# Microcontroller_board_Photodiode_plate.net
KiCad netlist of a schematic drawn in EasyEDA
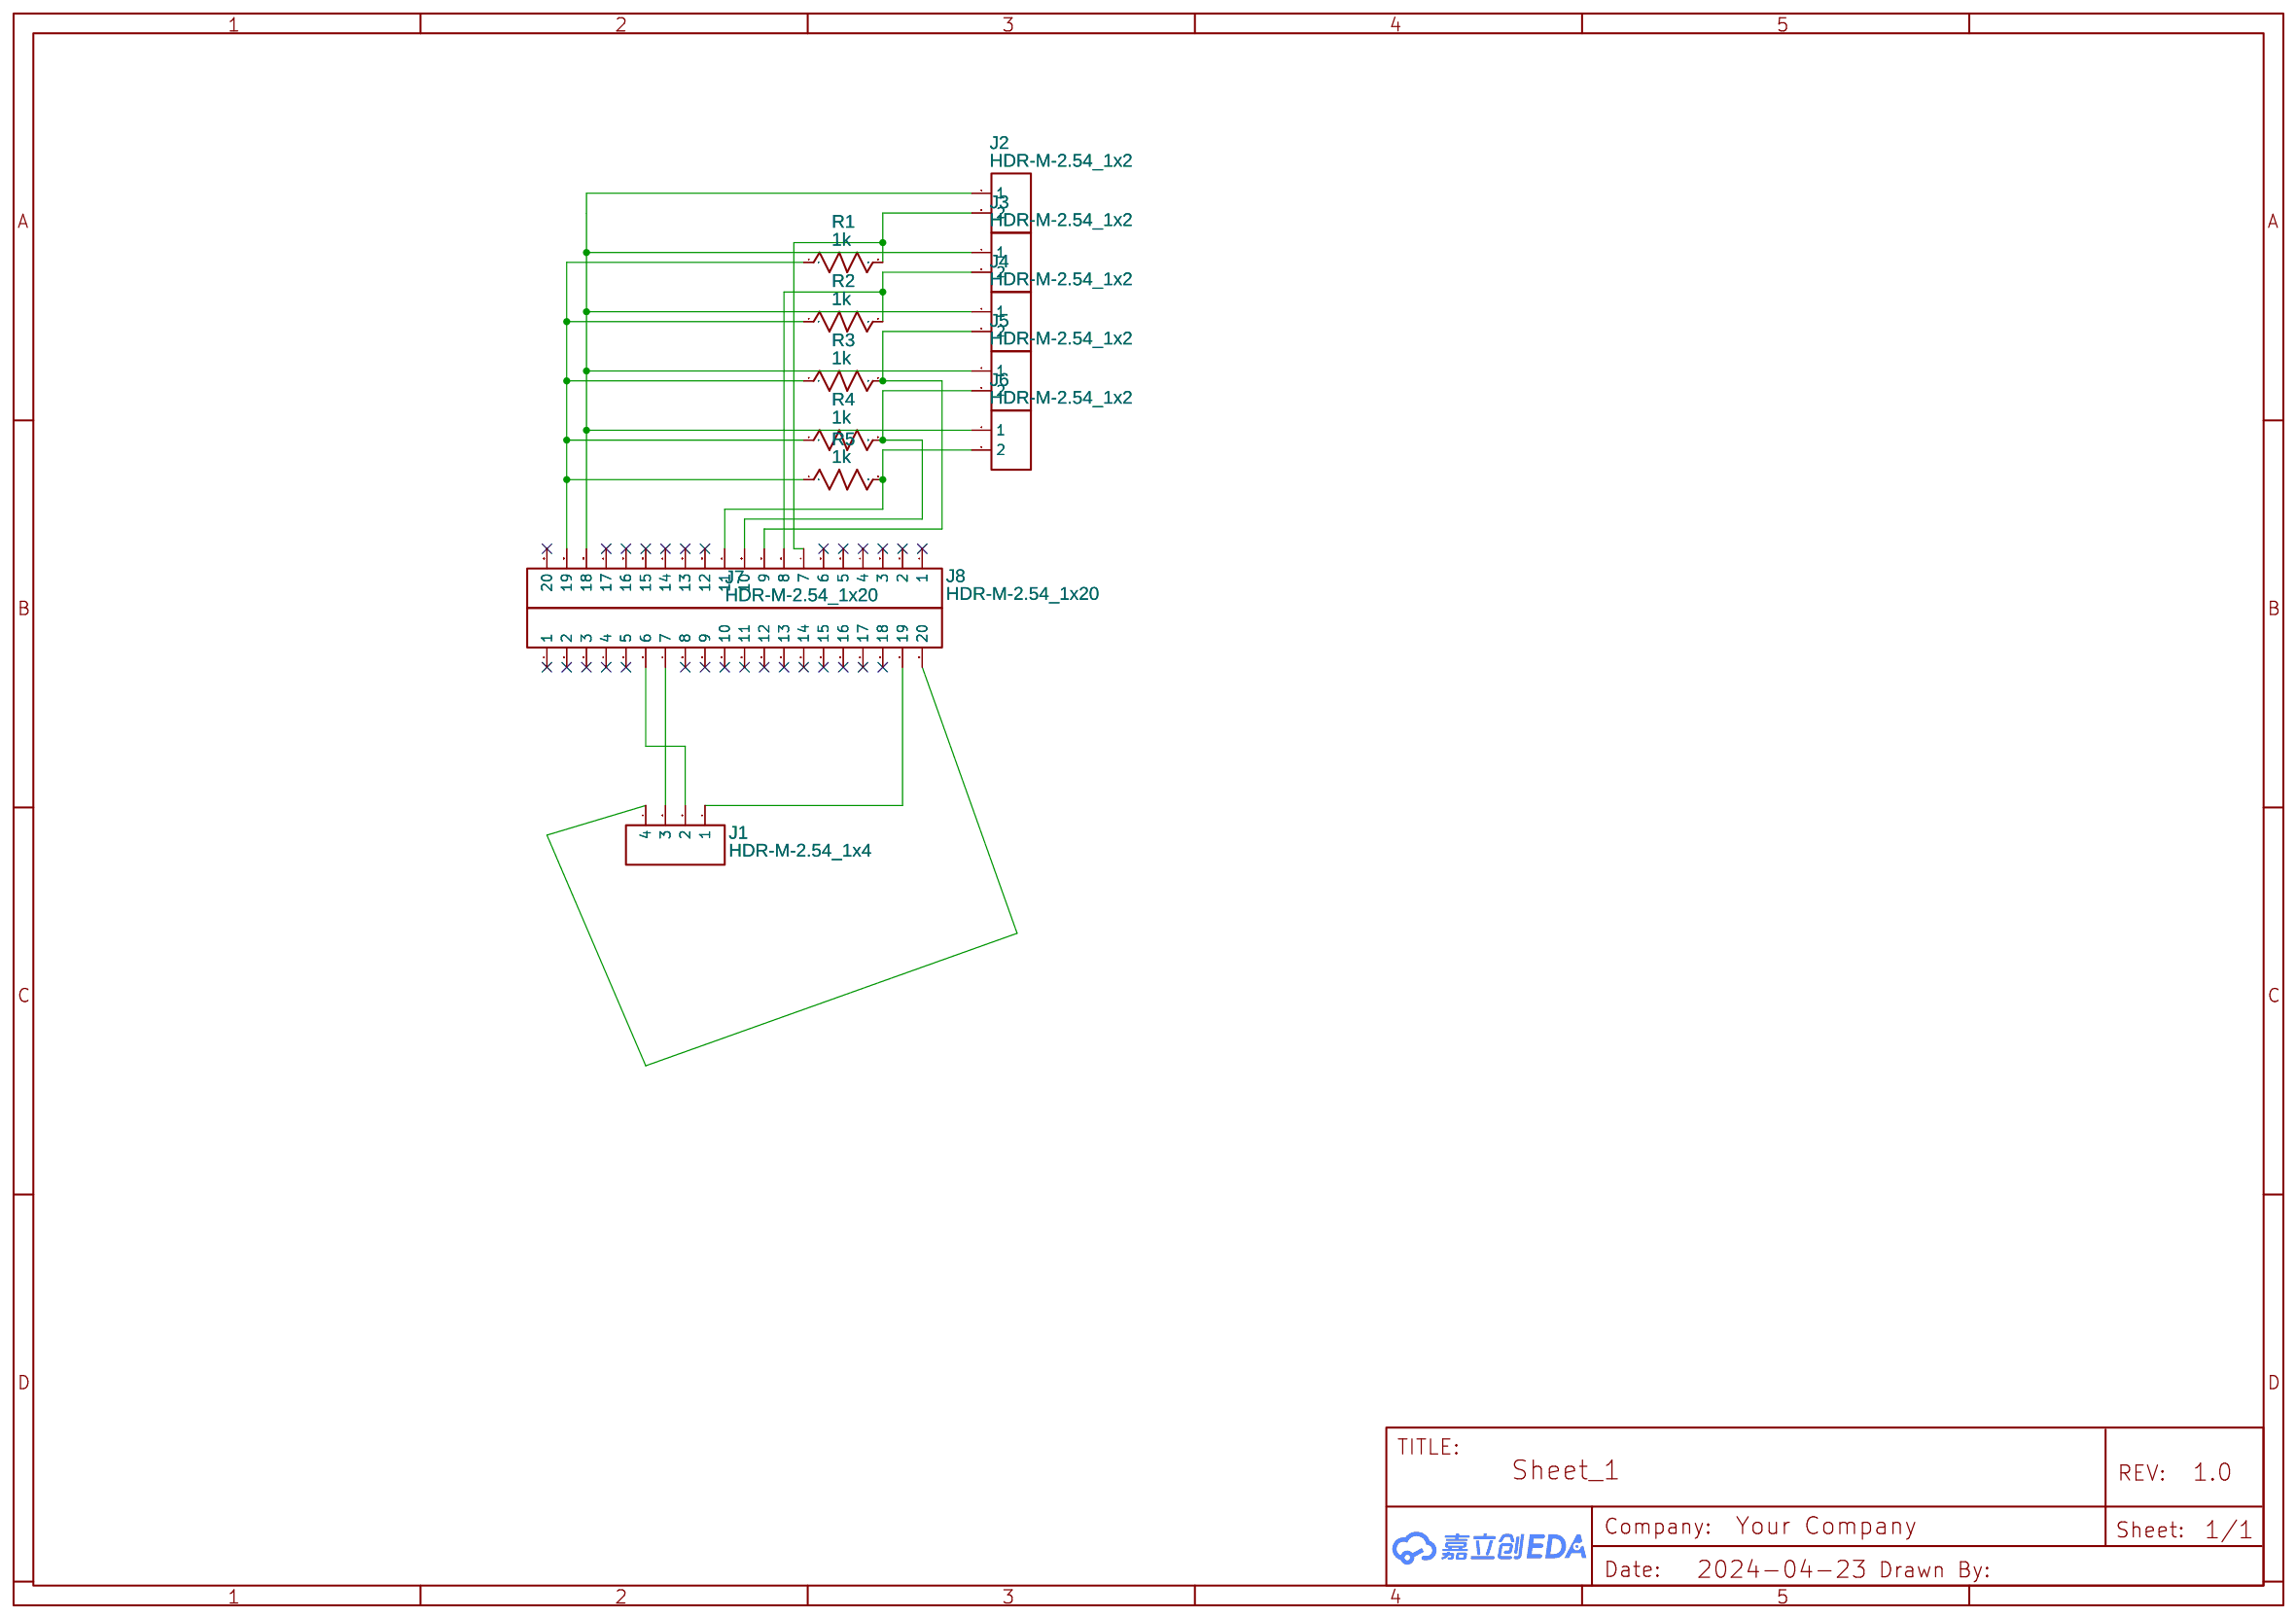
[diagram p0: schematic sheet]

(export (version "E")
  (design (tool "Eeschema 10.0.6"))
  (components
    (comp (ref "J1")
      (value "HDR-M-2.54_1x4")
      (fields (field (name "BOM_Supplier Part") "C124378"))
      (libsource (lib "") (part "HDR-M-2.54_1x4"))
    )
    (comp (ref "J2")
      (value "HDR-M-2.54_1x2")
      (fields (field (name "BOM_Supplier Part") "C124375"))
      (libsource (lib "") (part "HDR-M-2.54_1x2"))
    )
    (comp (ref "J3")
      (value "HDR-M-2.54_1x2")
      (fields (field (name "BOM_Supplier Part") "C124375"))
      (libsource (lib "") (part "HDR-M-2.54_1x2"))
    )
    (comp (ref "J4")
      (value "HDR-M-2.54_1x2")
      (fields (field (name "BOM_Supplier Part") "C124375"))
      (libsource (lib "") (part "HDR-M-2.54_1x2"))
    )
    (comp (ref "J5")
      (value "HDR-M-2.54_1x2")
      (fields (field (name "BOM_Supplier Part") "C124375"))
      (libsource (lib "") (part "HDR-M-2.54_1x2"))
    )
    (comp (ref "J6")
      (value "HDR-M-2.54_1x2")
      (fields (field (name "BOM_Supplier Part") "C124375"))
      (libsource (lib "") (part "HDR-M-2.54_1x2"))
    )
    (comp (ref "J7")
      (value "HDR-M-2.54_1x20")
      (fields (field (name "BOM_Supplier Part") "C50981"))
      (libsource (lib "") (part "HDR-M-2.54_1x20"))
    )
    (comp (ref "J8")
      (value "HDR-M-2.54_1x20")
      (fields (field (name "BOM_Supplier Part") "C50981"))
      (libsource (lib "") (part "HDR-M-2.54_1x20_1"))
    )
    (comp (ref "R1") (value "1k") (libsource (lib "") (part "R_AXIAL-0.3_US")))
    (comp (ref "R2") (value "1k") (libsource (lib "") (part "R_AXIAL-0.3_US")))
    (comp (ref "R3") (value "1k") (libsource (lib "") (part "R_AXIAL-0.3_US")))
    (comp (ref "R4") (value "1k") (libsource (lib "") (part "R_AXIAL-0.3_US")))
    (comp (ref "R5") (value "1k") (libsource (lib "") (part "R_AXIAL-0.4_US")))
  )
  (nets
    (net (code "1") (name "Net-(J1-Pad1)") (class "Default")
      (node (ref "J1") (pin "1") (pinfunction "1_1") (pintype "unspecified"))
      (node (ref "J7") (pin "19") (pinfunction "19_19") (pintype "unspecified"))
    )
    (net (code "2") (name "Net-(J1-Pad2)") (class "Default")
      (node (ref "J1") (pin "2") (pinfunction "2_2") (pintype "unspecified"))
      (node (ref "J7") (pin "6") (pinfunction "6_6") (pintype "unspecified"))
    )
    (net (code "3") (name "Net-(J1-Pad3)") (class "Default")
      (node (ref "J1") (pin "3") (pinfunction "3_3") (pintype "unspecified"))
      (node (ref "J7") (pin "7") (pinfunction "7_7") (pintype "unspecified"))
    )
    (net (code "4") (name "Net-(J1-Pad4)") (class "Default")
      (node (ref "J1") (pin "4") (pinfunction "4_4") (pintype "unspecified"))
      (node (ref "J7") (pin "20") (pinfunction "20_20") (pintype "unspecified"))
    )
    (net (code "5") (name "Net-(J2-Pad1)") (class "Default")
      (node (ref "J2") (pin "1") (pinfunction "1_1") (pintype "unspecified"))
      (node (ref "J3") (pin "1") (pinfunction "1_1") (pintype "unspecified"))
      (node (ref "J4") (pin "1") (pinfunction "1_1") (pintype "unspecified"))
      (node (ref "J5") (pin "1") (pinfunction "1_1") (pintype "unspecified"))
      (node (ref "J6") (pin "1") (pinfunction "1_1") (pintype "unspecified"))
      (node (ref "J8") (pin "18") (pinfunction "18_18") (pintype "unspecified"))
    )
    (net (code "6") (name "Net-(J2-Pad2)") (class "Default")
      (node (ref "J2") (pin "2") (pinfunction "2_2") (pintype "unspecified"))
      (node (ref "J8") (pin "7") (pinfunction "7_7") (pintype "unspecified"))
      (node (ref "R1") (pin "2") (pinfunction "2_2") (pintype "unspecified"))
    )
    (net (code "7") (name "Net-(J3-Pad2)") (class "Default")
      (node (ref "J3") (pin "2") (pinfunction "2_2") (pintype "unspecified"))
      (node (ref "J8") (pin "8") (pinfunction "8_8") (pintype "unspecified"))
      (node (ref "R2") (pin "2") (pinfunction "2_2") (pintype "unspecified"))
    )
    (net (code "8") (name "Net-(J4-Pad2)") (class "Default")
      (node (ref "J4") (pin "2") (pinfunction "2_2") (pintype "unspecified"))
      (node (ref "J8") (pin "9") (pinfunction "9_9") (pintype "unspecified"))
      (node (ref "R3") (pin "2") (pinfunction "2_2") (pintype "unspecified"))
    )
    (net (code "9") (name "Net-(J5-Pad2)") (class "Default")
      (node (ref "J5") (pin "2") (pinfunction "2_2") (pintype "unspecified"))
      (node (ref "J8") (pin "10") (pinfunction "10_10") (pintype "unspecified"))
      (node (ref "R4") (pin "2") (pinfunction "2_2") (pintype "unspecified"))
    )
    (net (code "10") (name "Net-(J6-Pad2)") (class "Default")
      (node (ref "J6") (pin "2") (pinfunction "2_2") (pintype "unspecified"))
      (node (ref "J8") (pin "11") (pinfunction "11_11") (pintype "unspecified"))
      (node (ref "R5") (pin "2") (pinfunction "2_2") (pintype "unspecified"))
    )
    (net (code "11") (name "Net-(J8-Pad19)") (class "Default")
      (node (ref "J8") (pin "19") (pinfunction "19_19") (pintype "unspecified"))
      (node (ref "R1") (pin "1") (pinfunction "1_1") (pintype "unspecified"))
      (node (ref "R2") (pin "1") (pinfunction "1_1") (pintype "unspecified"))
      (node (ref "R3") (pin "1") (pinfunction "1_1") (pintype "unspecified"))
      (node (ref "R4") (pin "1") (pinfunction "1_1") (pintype "unspecified"))
      (node (ref "R5") (pin "1") (pinfunction "1_1") (pintype "unspecified"))
    )
    (net (code "12") (name "unconnected-(J7-Pad1)") (class "Default")
      (node (ref "J7") (pin "1") (pinfunction "1_1") (pintype "unspecified+no_connect"))
    )
    (net (code "13") (name "unconnected-(J7-Pad2)") (class "Default")
      (node (ref "J7") (pin "2") (pinfunction "2_2") (pintype "unspecified+no_connect"))
    )
    (net (code "14") (name "unconnected-(J7-Pad3)") (class "Default")
      (node (ref "J7") (pin "3") (pinfunction "3_3") (pintype "unspecified+no_connect"))
    )
    (net (code "15") (name "unconnected-(J7-Pad4)") (class "Default")
      (node (ref "J7") (pin "4") (pinfunction "4_4") (pintype "unspecified+no_connect"))
    )
    (net (code "16") (name "unconnected-(J7-Pad5)") (class "Default")
      (node (ref "J7") (pin "5") (pinfunction "5_5") (pintype "unspecified+no_connect"))
    )
    (net (code "17") (name "unconnected-(J7-Pad8)") (class "Default")
      (node (ref "J7") (pin "8") (pinfunction "8_8") (pintype "unspecified+no_connect"))
    )
    (net (code "18") (name "unconnected-(J7-Pad9)") (class "Default")
      (node (ref "J7") (pin "9") (pinfunction "9_9") (pintype "unspecified+no_connect"))
    )
    (net (code "19") (name "unconnected-(J7-Pad10)") (class "Default")
      (node (ref "J7") (pin "10") (pinfunction "10_10") (pintype "unspecified+no_connect"))
    )
    (net (code "20") (name "unconnected-(J7-Pad11)") (class "Default")
      (node (ref "J7") (pin "11") (pinfunction "11_11") (pintype "unspecified+no_connect"))
    )
    (net (code "21") (name "unconnected-(J7-Pad12)") (class "Default")
      (node (ref "J7") (pin "12") (pinfunction "12_12") (pintype "unspecified+no_connect"))
    )
    (net (code "22") (name "unconnected-(J7-Pad13)") (class "Default")
      (node (ref "J7") (pin "13") (pinfunction "13_13") (pintype "unspecified+no_connect"))
    )
    (net (code "23") (name "unconnected-(J7-Pad14)") (class "Default")
      (node (ref "J7") (pin "14") (pinfunction "14_14") (pintype "unspecified+no_connect"))
    )
    (net (code "24") (name "unconnected-(J7-Pad15)") (class "Default")
      (node (ref "J7") (pin "15") (pinfunction "15_15") (pintype "unspecified+no_connect"))
    )
    (net (code "25") (name "unconnected-(J7-Pad16)") (class "Default")
      (node (ref "J7") (pin "16") (pinfunction "16_16") (pintype "unspecified+no_connect"))
    )
    (net (code "26") (name "unconnected-(J7-Pad17)") (class "Default")
      (node (ref "J7") (pin "17") (pinfunction "17_17") (pintype "unspecified+no_connect"))
    )
    (net (code "27") (name "unconnected-(J7-Pad18)") (class "Default")
      (node (ref "J7") (pin "18") (pinfunction "18_18") (pintype "unspecified+no_connect"))
    )
    (net (code "28") (name "unconnected-(J8-Pad1)") (class "Default")
      (node (ref "J8") (pin "1") (pinfunction "1_1") (pintype "unspecified+no_connect"))
    )
    (net (code "29") (name "unconnected-(J8-Pad2)") (class "Default")
      (node (ref "J8") (pin "2") (pinfunction "2_2") (pintype "unspecified+no_connect"))
    )
    (net (code "30") (name "unconnected-(J8-Pad3)") (class "Default")
      (node (ref "J8") (pin "3") (pinfunction "3_3") (pintype "unspecified+no_connect"))
    )
    (net (code "31") (name "unconnected-(J8-Pad4)") (class "Default")
      (node (ref "J8") (pin "4") (pinfunction "4_4") (pintype "unspecified+no_connect"))
    )
    (net (code "32") (name "unconnected-(J8-Pad5)") (class "Default")
      (node (ref "J8") (pin "5") (pinfunction "5_5") (pintype "unspecified+no_connect"))
    )
    (net (code "33") (name "unconnected-(J8-Pad6)") (class "Default")
      (node (ref "J8") (pin "6") (pinfunction "6_6") (pintype "unspecified+no_connect"))
    )
    (net (code "34") (name "unconnected-(J8-Pad12)") (class "Default")
      (node (ref "J8") (pin "12") (pinfunction "12_12") (pintype "unspecified+no_connect"))
    )
    (net (code "35") (name "unconnected-(J8-Pad13)") (class "Default")
      (node (ref "J8") (pin "13") (pinfunction "13_13") (pintype "unspecified+no_connect"))
    )
    (net (code "36") (name "unconnected-(J8-Pad14)") (class "Default")
      (node (ref "J8") (pin "14") (pinfunction "14_14") (pintype "unspecified+no_connect"))
    )
    (net (code "37") (name "unconnected-(J8-Pad15)") (class "Default")
      (node (ref "J8") (pin "15") (pinfunction "15_15") (pintype "unspecified+no_connect"))
    )
    (net (code "38") (name "unconnected-(J8-Pad16)") (class "Default")
      (node (ref "J8") (pin "16") (pinfunction "16_16") (pintype "unspecified+no_connect"))
    )
    (net (code "39") (name "unconnected-(J8-Pad17)") (class "Default")
      (node (ref "J8") (pin "17") (pinfunction "17_17") (pintype "unspecified+no_connect"))
    )
    (net (code "40") (name "unconnected-(J8-Pad20)") (class "Default")
      (node (ref "J8") (pin "20") (pinfunction "20_20") (pintype "unspecified+no_connect"))
    )
  )
)
